# MergenElektronik_Developing-Board_ESP32.net
KiCad netlist of a schematic drawn in EAGLE
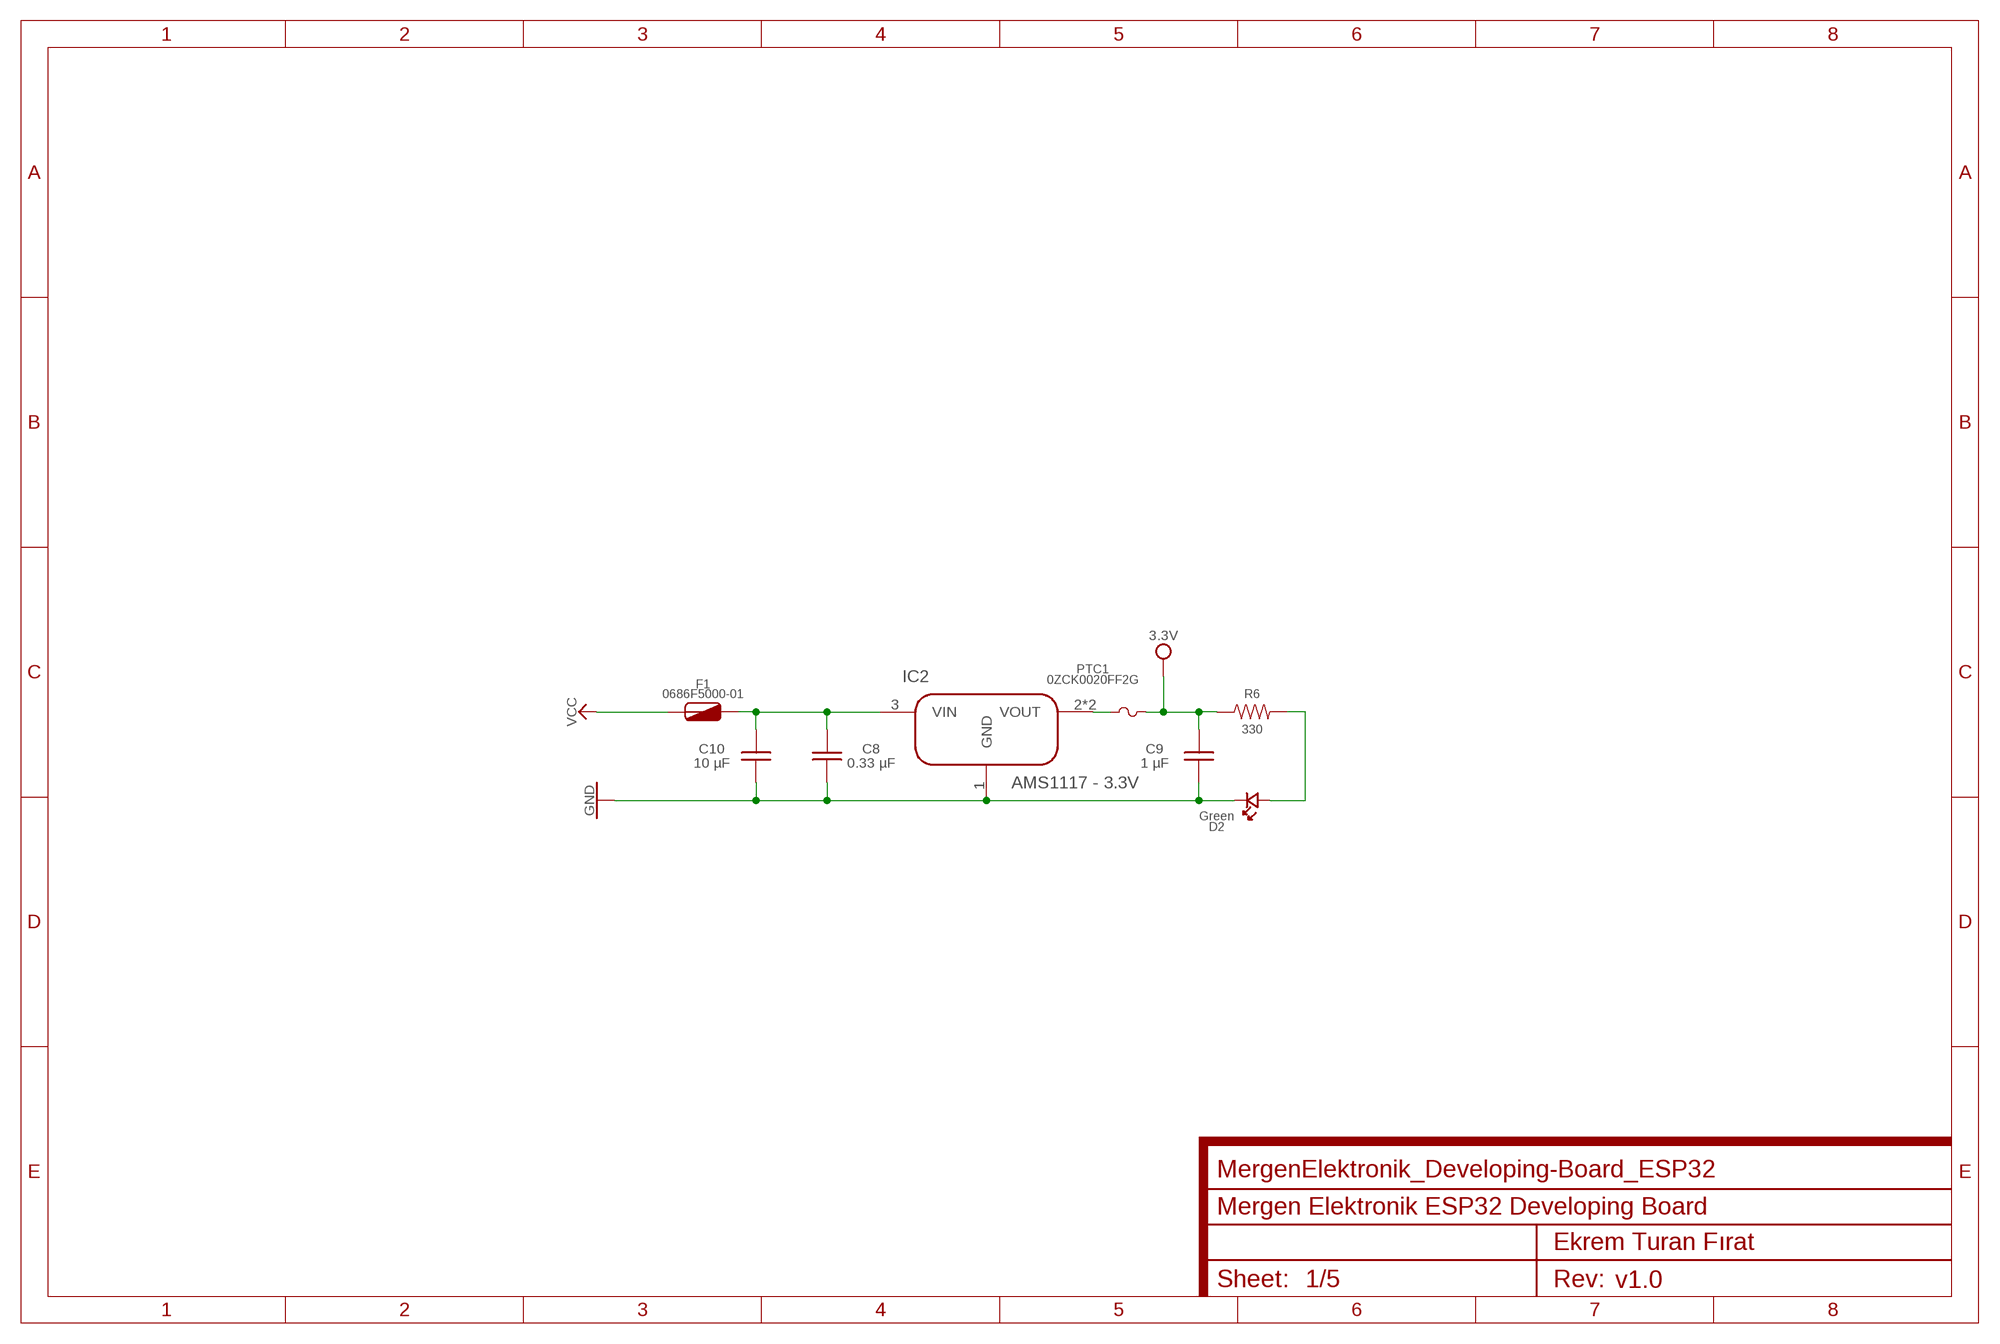
[diagram p0: schematic, sheet 1]
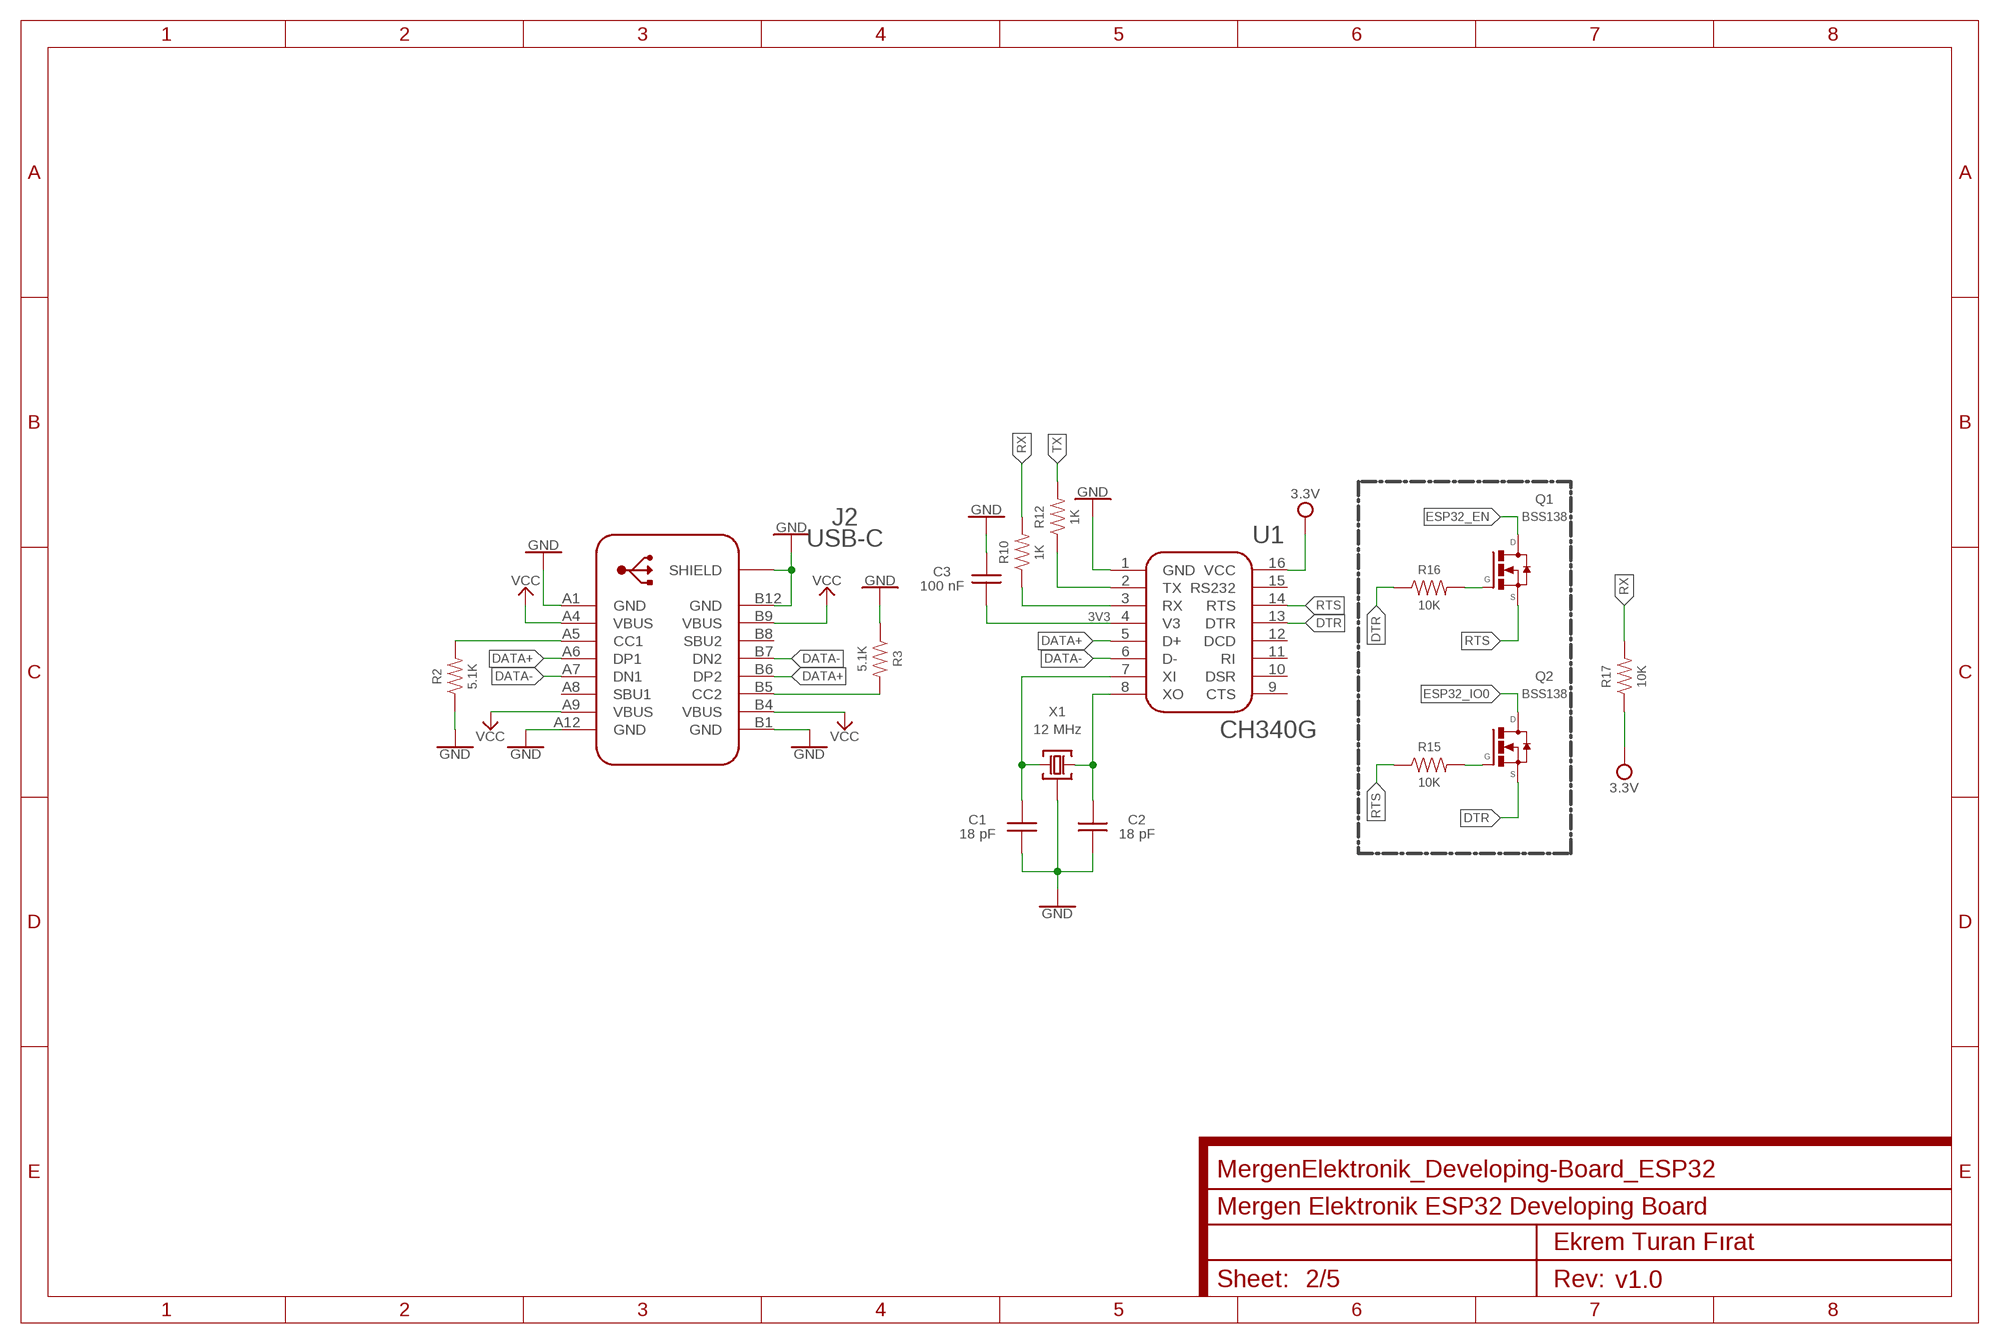
[diagram p1: schematic, sheet 2]
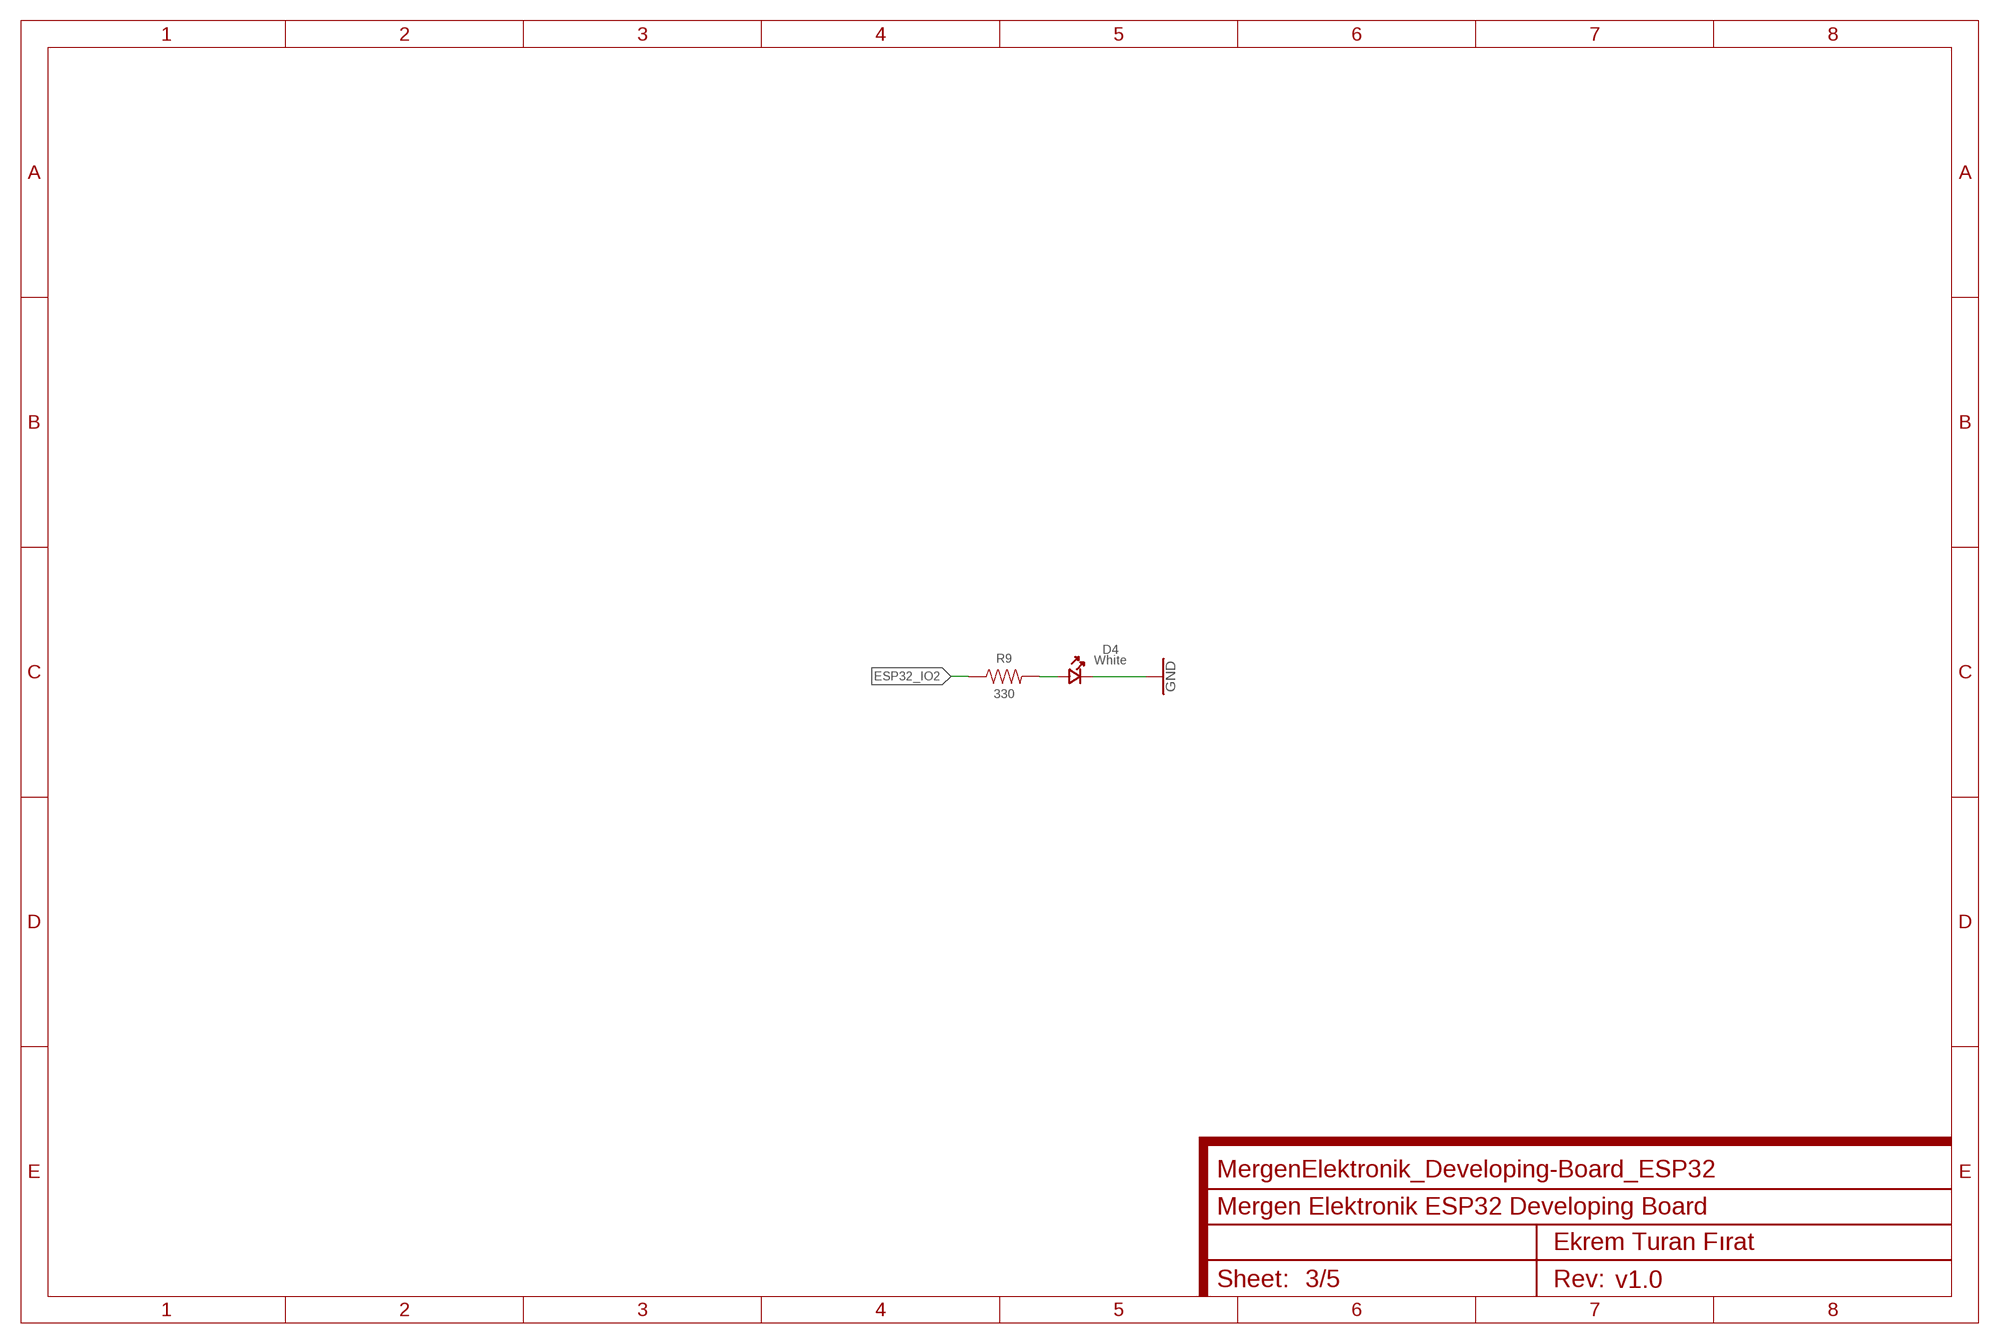
[diagram p2: schematic, sheet 3]
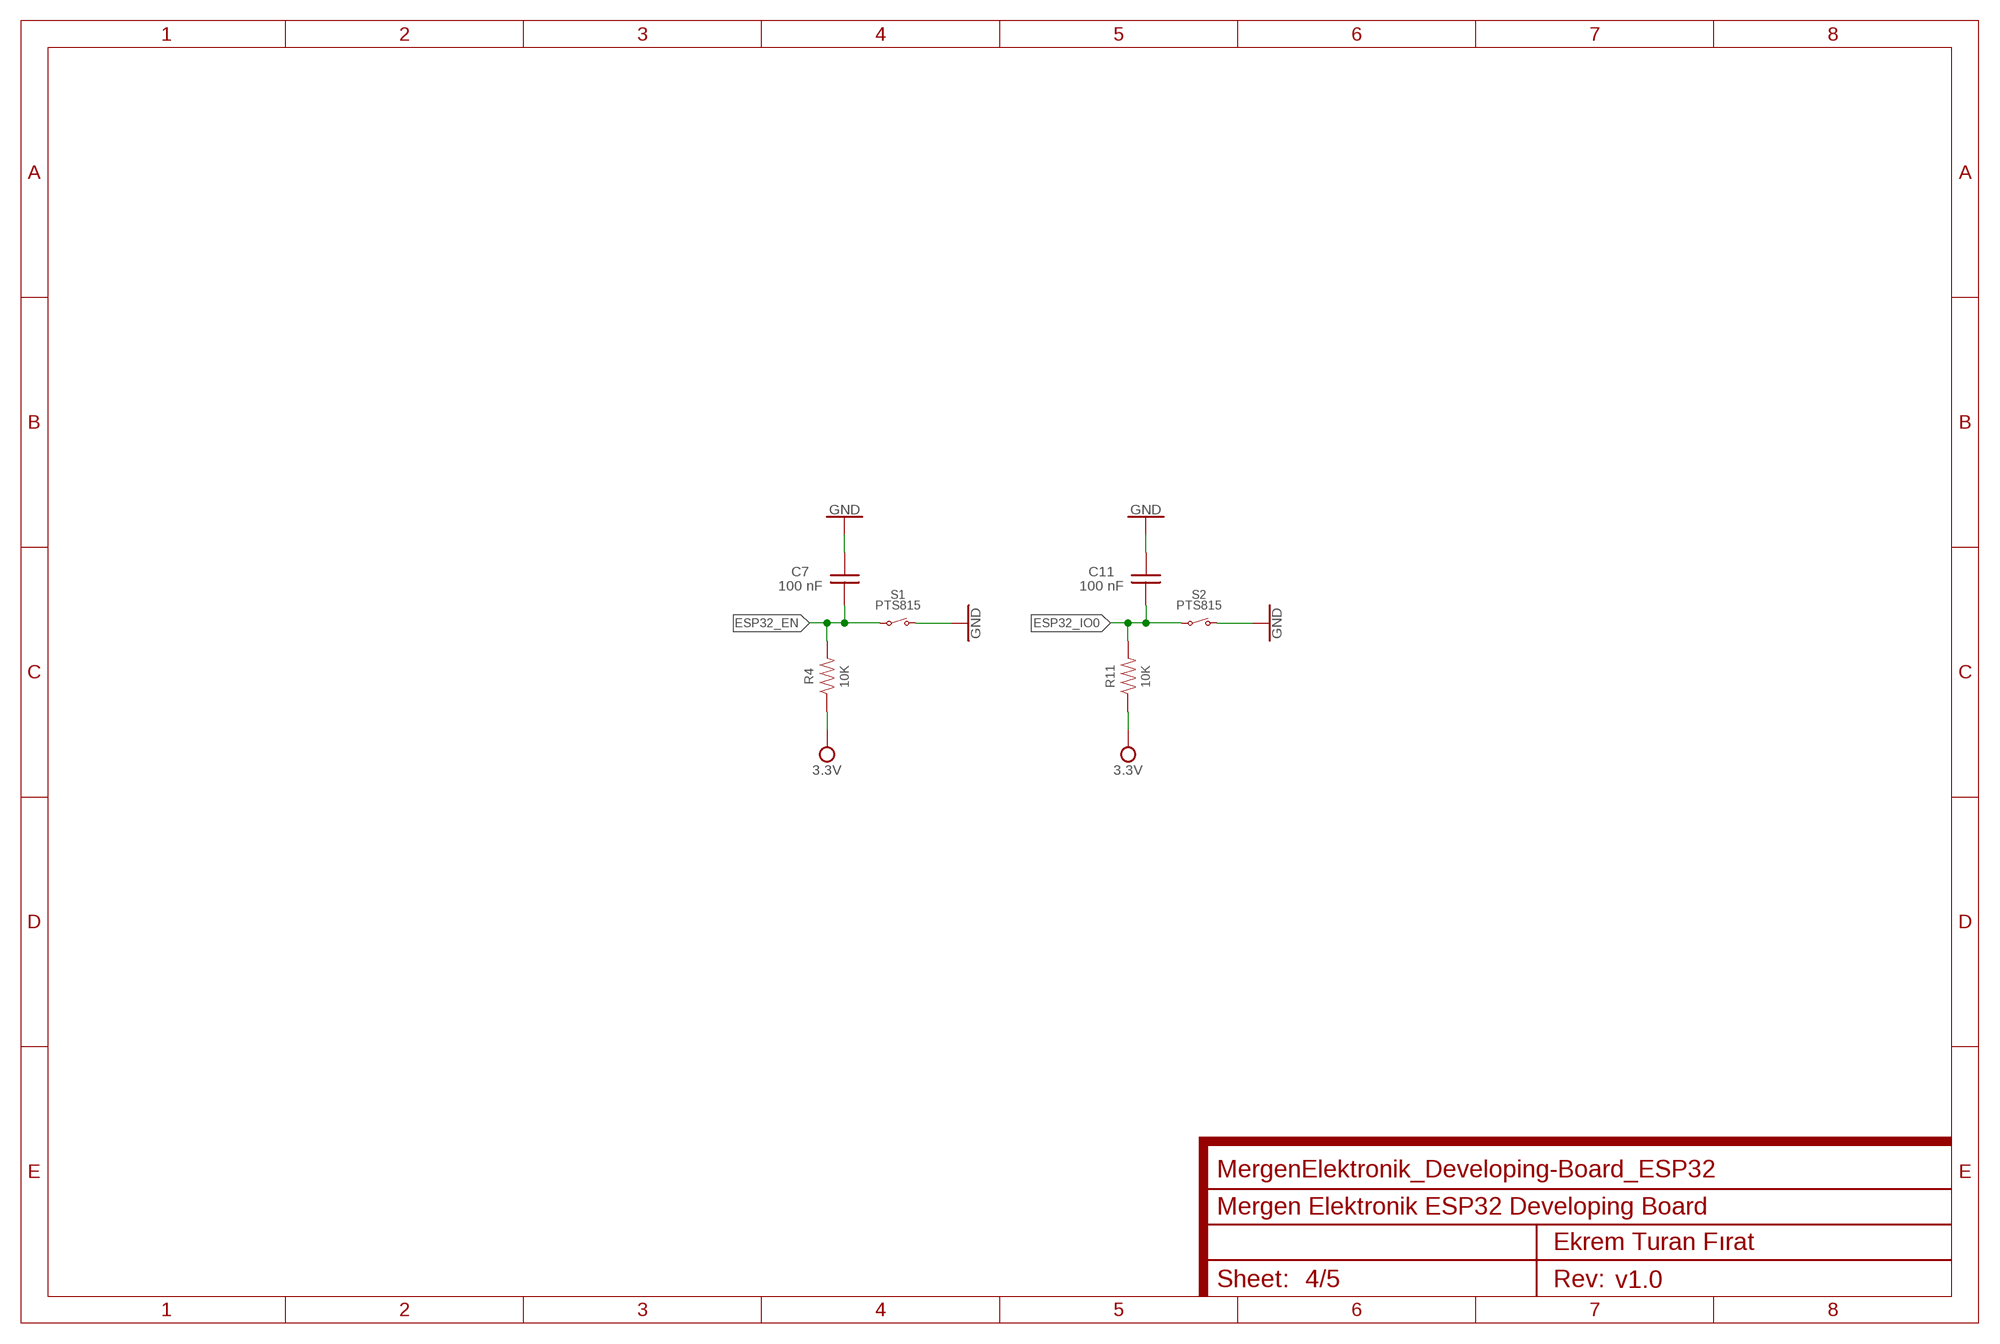
[diagram p3: schematic, sheet 4]
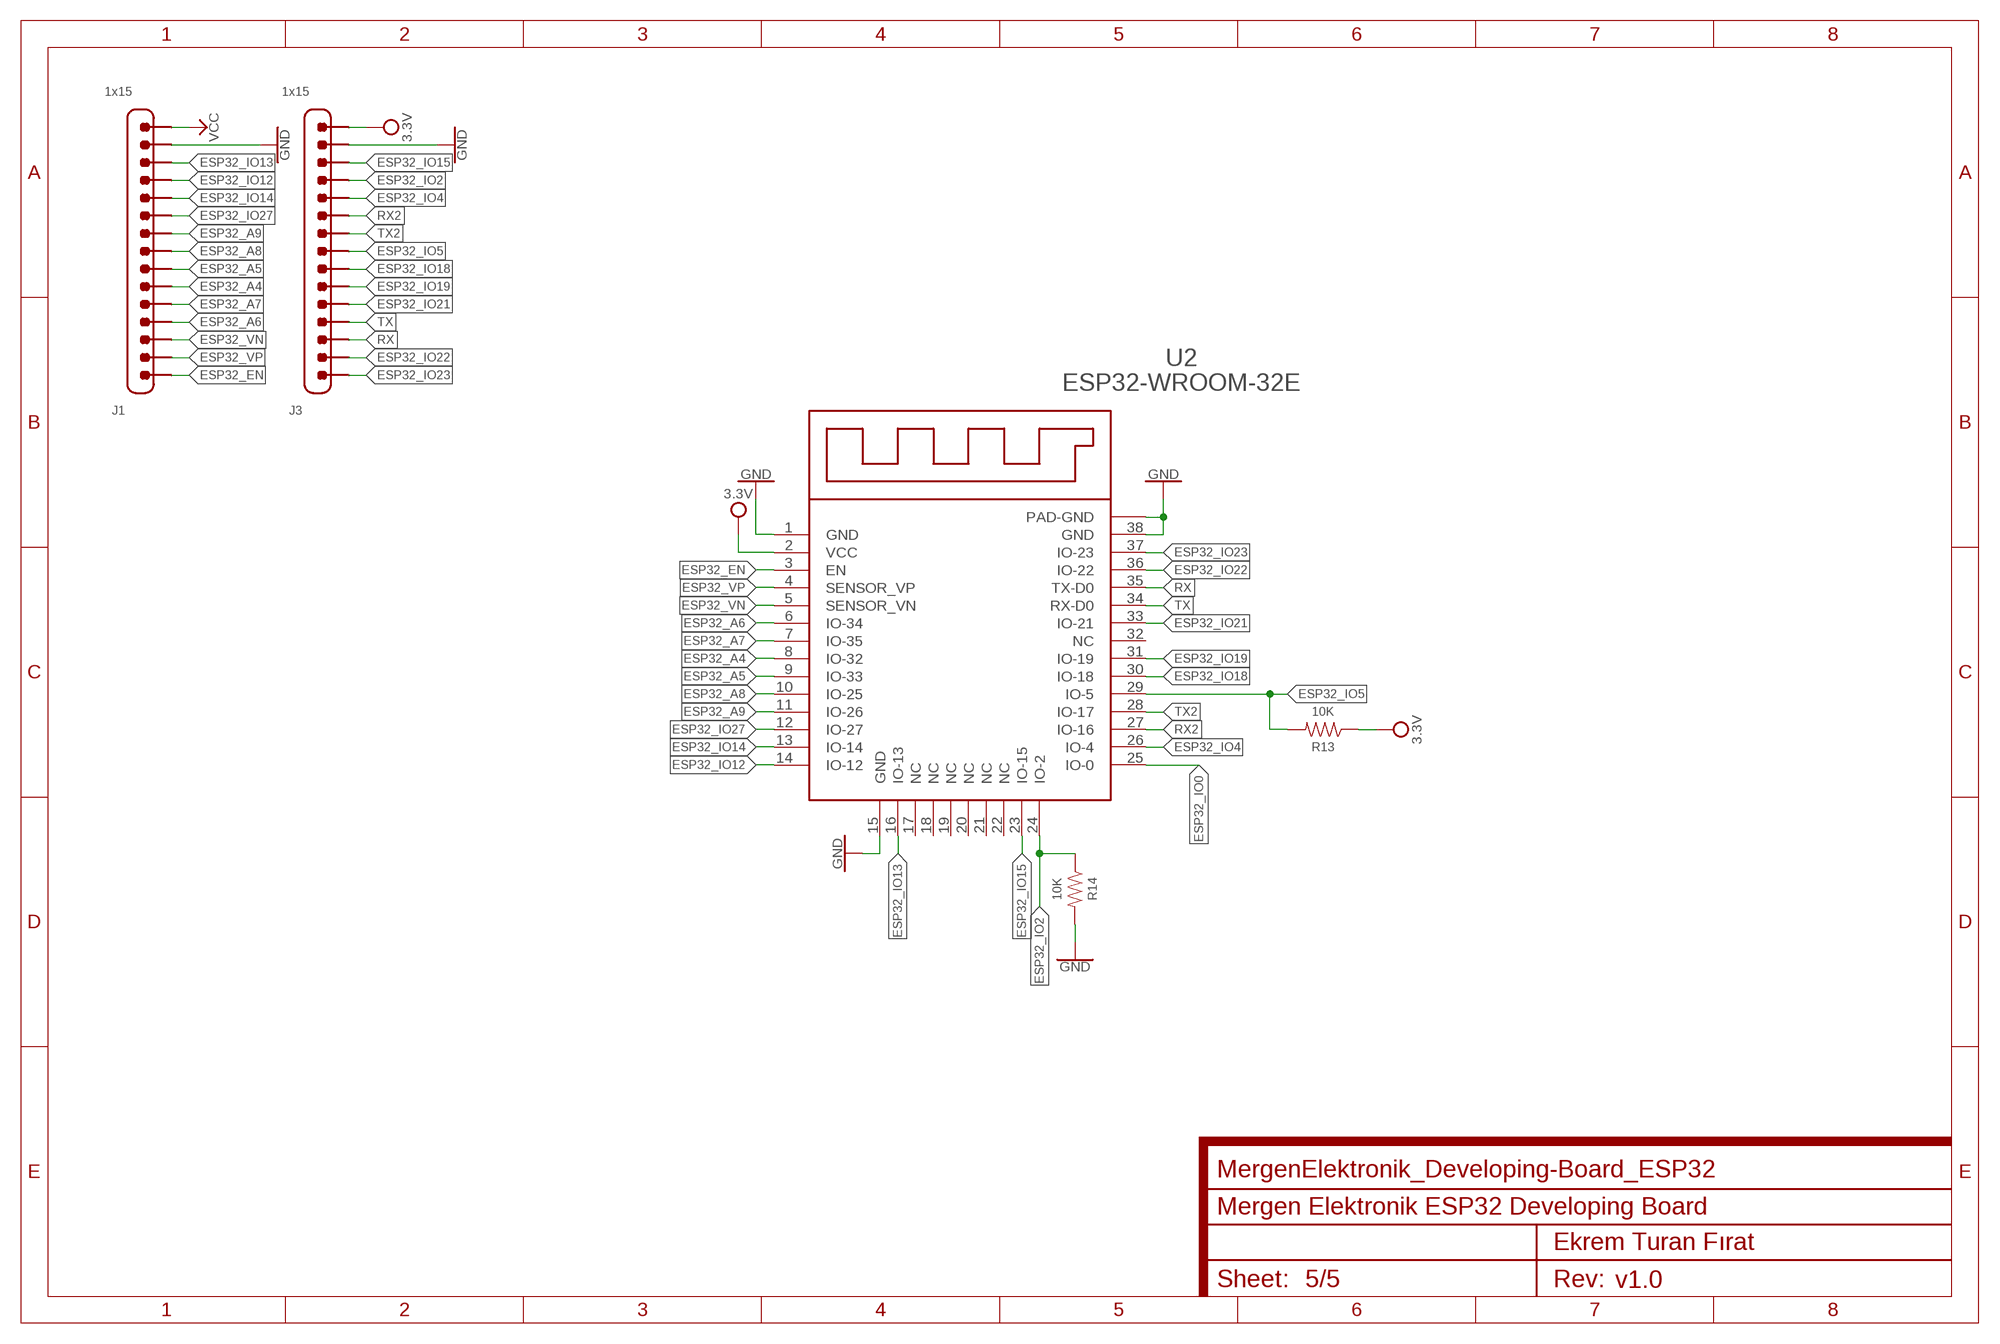
[diagram p4: schematic, sheet 5]

(export (version "E")
  (design (tool "Eeschema 10.0.6"))
  (components
    (comp (ref "C1")
      (value "18 pF")
      (footprint "eagle-import:0603")
      (fields (field (name "TOLERANCE") "5%") (field (name "VOLTAGE") "50V"))
      (libsource (lib "eagle-import") (part "NACHTELK_CAP-NONPOLAR-SMD_0603_18PF"))
    )
    (comp (ref "C2")
      (value "18 pF")
      (footprint "eagle-import:0603")
      (fields (field (name "TOLERANCE") "5%") (field (name "VOLTAGE") "50V"))
      (libsource (lib "eagle-import") (part "NACHTELK_CAP-NONPOLAR-SMD_0603_18PF"))
    )
    (comp (ref "C3")
      (value "100 nF")
      (footprint "eagle-import:0603")
      (fields (field (name "TOLERANCE") "10%") (field (name "VOLTAGE") "50V"))
      (libsource (lib "eagle-import") (part "NACHTELK_CAP-NONPOLAR-SMD_0603_100NF"))
    )
    (comp (ref "J2")
      (value "USB-C")
      (footprint "eagle-import:USB4105")
      (libsource (lib "eagle-import") (part "NACHTELK_USBCONNECTORS_C-USB4105"))
    )
    (comp (ref "Q1")
      (value "BSS138")
      (footprint "eagle-import:SOT-23")
      (libsource (lib "eagle-import") (part "NACHTELK_MOSFET_N-CH_SOT-23_STYLE-21_BSS138"))
    )
    (comp (ref "Q2")
      (value "BSS138")
      (footprint "eagle-import:SOT-23")
      (libsource (lib "eagle-import") (part "NACHTELK_MOSFET_N-CH_SOT-23_STYLE-21_BSS138"))
    )
    (comp (ref "R2")
      (value "5.1K")
      (footprint "eagle-import:0603")
      (fields (field (name "POWER") "1/10W") (field (name "TOLERANCE") "%1"))
      (libsource (lib "eagle-import") (part "NACHTELK_RES-SMD_0603_5.1K"))
    )
    (comp (ref "R3")
      (value "5.1K")
      (footprint "eagle-import:0603")
      (fields (field (name "POWER") "1/10W") (field (name "TOLERANCE") "%1"))
      (libsource (lib "eagle-import") (part "NACHTELK_RES-SMD_0603_5.1K"))
    )
    (comp (ref "R10")
      (value "1K")
      (footprint "eagle-import:0603")
      (fields (field (name "POWER") "1/10W") (field (name "TOLERANCE") "%5"))
      (libsource (lib "eagle-import") (part "NACHTELK_RES-SMD_0603_1K"))
    )
    (comp (ref "R12")
      (value "1K")
      (footprint "eagle-import:0603")
      (fields (field (name "POWER") "1/10W") (field (name "TOLERANCE") "%5"))
      (libsource (lib "eagle-import") (part "NACHTELK_RES-SMD_0603_1K"))
    )
    (comp (ref "R15")
      (value "10K")
      (footprint "eagle-import:0603")
      (fields (field (name "POWER") "1/10W") (field (name "TOLERANCE") "%5"))
      (libsource (lib "eagle-import") (part "NACHTELK_RES-SMD_0603_10K"))
    )
    (comp (ref "R16")
      (value "10K")
      (footprint "eagle-import:0603")
      (fields (field (name "POWER") "1/10W") (field (name "TOLERANCE") "%5"))
      (libsource (lib "eagle-import") (part "NACHTELK_RES-SMD_0603_10K"))
    )
    (comp (ref "R17")
      (value "10K")
      (footprint "eagle-import:0603")
      (fields (field (name "POWER") "1/10W") (field (name "TOLERANCE") "%5"))
      (libsource (lib "eagle-import") (part "NACHTELK_RES-SMD_0603_10K"))
    )
    (comp (ref "U1")
      (value "CH340G")
      (footprint "eagle-import:SOIC-16")
      (fields (field (name "VOLTAGE") "3.3V and 5V"))
      (libsource (lib "eagle-import") (part "NACHTELK_COMMUNICATION-UART_CH340"))
    )
    (comp (ref "X1")
      (value "12 MHz")
      (footprint "eagle-import:4-SMD")
      (fields (field (name "TOLERANCE") "±20ppm"))
      (libsource (lib "eagle-import") (part "NACHTELK_CRYSTALS_EXTERNAL-G"))
    )
    (comp (ref "D4")
      (value "White")
      (footprint "eagle-import:0603_WHİTE")
      (fields (field (name "VOLTAGE") "3.2V"))
      (libsource (lib "eagle-import") (part "NACHTELK_LED_SMD_0603_WHITE"))
    )
    (comp (ref "R9")
      (value "330")
      (footprint "eagle-import:0603")
      (fields (field (name "POWER") "1/10W") (field (name "TOLERANCE") "%5"))
      (libsource (lib "eagle-import") (part "NACHTELK_RES-SMD_0603_330R"))
    )
    (comp (ref "C8")
      (value "0.33 µF")
      (footprint "eagle-import:0603")
      (fields (field (name "TOLERANCE") "10%") (field (name "VOLTAGE") "50V"))
      (libsource (lib "eagle-import") (part "NACHTELK_CAP-NONPOLAR-SMD_0603_0.33UF"))
    )
    (comp (ref "C9")
      (value "1 µF")
      (footprint "eagle-import:0603")
      (fields (field (name "TOLERANCE") "10%") (field (name "VOLTAGE") "50V"))
      (libsource (lib "eagle-import") (part "NACHTELK_CAP-NONPOLAR-SMD_0603_1UF"))
    )
    (comp (ref "C10")
      (value "10 µF")
      (footprint "eagle-import:0603")
      (fields (field (name "TOLERANCE") "10%") (field (name "VOLTAGE") "25V"))
      (libsource (lib "eagle-import") (part "NACHTELK_CAP-NONPOLAR-SMD_0603_10UF"))
    )
    (comp (ref "D2")
      (value "Green")
      (footprint "eagle-import:0603_GREEN")
      (fields (field (name "VOLTAGE") "3.2V"))
      (libsource (lib "eagle-import") (part "NACHTELK_LED_SMD_0603_GREEN"))
    )
    (comp (ref "F1")
      (value "0686F5000-01")
      (footprint "eagle-import:0603")
      (libsource (lib "eagle-import") (part "NACHTELK_FUSES_SMD_0603_5A"))
    )
    (comp (ref "IC2")
      (value "AMS1117 - 3.3V")
      (footprint "eagle-import:SOT-223")
      (libsource (lib "eagle-import") (part "NACHTELK_LINEAR-REG_AMS1117_3.3V"))
    )
    (comp (ref "PTC1")
      (value "0ZCK0020FF2G")
      (footprint "eagle-import:0805")
      (fields (field (name "VOLTAGE") "9V"))
      (libsource (lib "eagle-import") (part "NACHHTELK_PTCS-SMD_0805_0ZCK0020FF2G"))
    )
    (comp (ref "R6")
      (value "330")
      (footprint "eagle-import:0603")
      (fields (field (name "POWER") "1/10W") (field (name "TOLERANCE") "%5"))
      (libsource (lib "eagle-import") (part "NACHTELK_RES-SMD_0603_330R"))
    )
    (comp (ref "C7")
      (value "100 nF")
      (footprint "eagle-import:0603")
      (fields (field (name "TOLERANCE") "10%") (field (name "VOLTAGE") "50V"))
      (libsource (lib "eagle-import") (part "NACHTELK_CAP-NONPOLAR-SMD_0603_100NF"))
    )
    (comp (ref "C11")
      (value "100 nF")
      (footprint "eagle-import:0603")
      (fields (field (name "TOLERANCE") "10%") (field (name "VOLTAGE") "50V"))
      (libsource (lib "eagle-import") (part "NACHTELK_CAP-NONPOLAR-SMD_0603_100NF"))
    )
    (comp (ref "R4")
      (value "10K")
      (footprint "eagle-import:0603")
      (fields (field (name "POWER") "1/10W") (field (name "TOLERANCE") "%5"))
      (libsource (lib "eagle-import") (part "NACHTELK_RES-SMD_0603_10K"))
    )
    (comp (ref "R11")
      (value "10K")
      (footprint "eagle-import:0603")
      (fields (field (name "POWER") "1/10W") (field (name "TOLERANCE") "%5"))
      (libsource (lib "eagle-import") (part "NACHTELK_RES-SMD_0603_10K"))
    )
    (comp (ref "S1")
      (value "PTS815")
      (footprint "eagle-import:PTS815")
      (fields (field (name "VOLTAGE") "12V"))
      (libsource (lib "eagle-import") (part "NACHTELK_BUTTONS_BUTTON_PTS815_PTS815"))
    )
    (comp (ref "S2")
      (value "PTS815")
      (footprint "eagle-import:PTS815")
      (fields (field (name "VOLTAGE") "12V"))
      (libsource (lib "eagle-import") (part "NACHTELK_BUTTONS_BUTTON_PTS815_PTS815"))
    )
    (comp (ref "J1")
      (value "1x15")
      (footprint "eagle-import:HEADER_1X15")
      (libsource (lib "eagle-import") (part "NACHTELK_HEADERCONNECTORS_15_MALE"))
    )
    (comp (ref "J3")
      (value "1x15")
      (footprint "eagle-import:HEADER_1X15")
      (libsource (lib "eagle-import") (part "NACHTELK_HEADERCONNECTORS_15_MALE"))
    )
    (comp (ref "R13")
      (value "10K")
      (footprint "eagle-import:0603")
      (fields (field (name "POWER") "1/10W") (field (name "TOLERANCE") "%5"))
      (libsource (lib "eagle-import") (part "NACHTELK_RES-SMD_0603_10K"))
    )
    (comp (ref "R14")
      (value "10K")
      (footprint "eagle-import:0603")
      (fields (field (name "POWER") "1/10W") (field (name "TOLERANCE") "%5"))
      (libsource (lib "eagle-import") (part "NACHTELK_RES-SMD_0603_10K"))
    )
    (comp (ref "U2")
      (value "ESP32-WROOM-32E")
      (footprint "eagle-import:38-SMD_MODULE")
      (fields (field (name "VOLTAGE") "3V up to 3,6"))
      (libsource (lib "eagle-import") (part "NACHTELK_MICROCONTROLLER_ESP_ESP32_WROOM_32E"))
    )
  )
  (nets
    (net (code "1") (name "3V3") (class "Default")
      (node (ref "C3") (pin "2") (pinfunction "2_2") (pintype "passive"))
      (node (ref "C9") (pin "1") (pinfunction "1_1") (pintype "passive"))
      (node (ref "J3") (pin "1") (pinfunction "P$1_1") (pintype "bidirectional"))
      (node (ref "PTC1") (pin "2") (pinfunction "2_2") (pintype "passive"))
      (node (ref "R11") (pin "1") (pinfunction "1_1") (pintype "passive"))
      (node (ref "R13") (pin "1") (pinfunction "1_1") (pintype "passive"))
      (node (ref "R17") (pin "1") (pinfunction "1_1") (pintype "passive"))
      (node (ref "R4") (pin "1") (pinfunction "1_1") (pintype "passive"))
      (node (ref "R6") (pin "1") (pinfunction "1_1") (pintype "passive"))
      (node (ref "U1") (pin "16") (pinfunction "VCC_16") (pintype "power_in"))
      (node (ref "U1") (pin "4") (pinfunction "V3_4") (pintype "bidirectional"))
      (node (ref "U2") (pin "2") (pinfunction "VCC_2") (pintype "power_in"))
    )
    (net (code "2") (name "DATA+") (class "Default")
      (node (ref "J2") (pin "A6") (pinfunction "DP1_A6") (pintype "bidirectional"))
      (node (ref "J2") (pin "B6") (pinfunction "DP2_B6") (pintype "bidirectional"))
      (node (ref "U1") (pin "5") (pinfunction "D+_5") (pintype "bidirectional"))
    )
    (net (code "3") (name "DATA-") (class "Default")
      (node (ref "J2") (pin "A7") (pinfunction "DN1_A7") (pintype "bidirectional"))
      (node (ref "J2") (pin "B7") (pinfunction "DN2_B7") (pintype "bidirectional"))
      (node (ref "U1") (pin "6") (pinfunction "D-_6") (pintype "bidirectional"))
    )
    (net (code "4") (name "DTR") (class "Default")
      (node (ref "Q2") (pin "2") (pinfunction "S_2") (pintype "passive"))
      (node (ref "R16") (pin "1") (pinfunction "1_1") (pintype "passive"))
      (node (ref "U1") (pin "13") (pinfunction "DTR_13") (pintype "bidirectional"))
    )
    (net (code "5") (name "ESP32_A4") (class "Default")
      (node (ref "J1") (pin "10") (pinfunction "P$10_10") (pintype "bidirectional"))
      (node (ref "U2") (pin "8") (pinfunction "IO-32_8") (pintype "bidirectional"))
    )
    (net (code "6") (name "ESP32_A5") (class "Default")
      (node (ref "J1") (pin "9") (pinfunction "P$9_9") (pintype "bidirectional"))
      (node (ref "U2") (pin "9") (pinfunction "IO-33_9") (pintype "bidirectional"))
    )
    (net (code "7") (name "ESP32_A6") (class "Default")
      (node (ref "J1") (pin "12") (pinfunction "P$12_12") (pintype "bidirectional"))
      (node (ref "U2") (pin "6") (pinfunction "IO-34_6") (pintype "bidirectional"))
    )
    (net (code "8") (name "ESP32_A7") (class "Default")
      (node (ref "J1") (pin "11") (pinfunction "P$11_11") (pintype "bidirectional"))
      (node (ref "U2") (pin "7") (pinfunction "IO-35_7") (pintype "bidirectional"))
    )
    (net (code "9") (name "ESP32_A8") (class "Default")
      (node (ref "J1") (pin "8") (pinfunction "P$8_8") (pintype "bidirectional"))
      (node (ref "U2") (pin "10") (pinfunction "IO-25_10") (pintype "bidirectional"))
    )
    (net (code "10") (name "ESP32_A9") (class "Default")
      (node (ref "J1") (pin "7") (pinfunction "P$7_7") (pintype "bidirectional"))
      (node (ref "U2") (pin "11") (pinfunction "IO-26_11") (pintype "bidirectional"))
    )
    (net (code "11") (name "ESP32_EN") (class "Default")
      (node (ref "C7") (pin "2") (pinfunction "2_2") (pintype "passive"))
      (node (ref "J1") (pin "15") (pinfunction "P$15_15") (pintype "bidirectional"))
      (node (ref "Q1") (pin "3") (pinfunction "D_3") (pintype "passive"))
      (node (ref "R4") (pin "2") (pinfunction "2_2") (pintype "passive"))
      (node (ref "S1") (pin "1") (pinfunction "PASS1_1") (pintype "bidirectional"))
      (node (ref "S1") (pin "2") (pinfunction "PASS1_2") (pintype "bidirectional"))
      (node (ref "U2") (pin "3") (pinfunction "EN_3") (pintype "input"))
    )
    (net (code "12") (name "ESP32_IO0") (class "Default")
      (node (ref "C11") (pin "2") (pinfunction "2_2") (pintype "passive"))
      (node (ref "Q2") (pin "3") (pinfunction "D_3") (pintype "passive"))
      (node (ref "R11") (pin "2") (pinfunction "2_2") (pintype "passive"))
      (node (ref "S2") (pin "1") (pinfunction "PASS1_1") (pintype "bidirectional"))
      (node (ref "S2") (pin "2") (pinfunction "PASS1_2") (pintype "bidirectional"))
      (node (ref "U2") (pin "25") (pinfunction "IO-0_25") (pintype "bidirectional"))
    )
    (net (code "13") (name "ESP32_IO2") (class "Default")
      (node (ref "J3") (pin "4") (pinfunction "P$4_4") (pintype "bidirectional"))
      (node (ref "R14") (pin "1") (pinfunction "1_1") (pintype "passive"))
      (node (ref "R9") (pin "1") (pinfunction "1_1") (pintype "passive"))
      (node (ref "U2") (pin "24") (pinfunction "IO-2_24") (pintype "bidirectional"))
    )
    (net (code "14") (name "ESP32_IO4") (class "Default")
      (node (ref "J3") (pin "5") (pinfunction "P$5_5") (pintype "bidirectional"))
      (node (ref "U2") (pin "26") (pinfunction "IO-4_26") (pintype "bidirectional"))
    )
    (net (code "15") (name "ESP32_IO5") (class "Default")
      (node (ref "J3") (pin "8") (pinfunction "P$8_8") (pintype "bidirectional"))
      (node (ref "R13") (pin "2") (pinfunction "2_2") (pintype "passive"))
      (node (ref "U2") (pin "29") (pinfunction "IO-5_29") (pintype "bidirectional"))
    )
    (net (code "16") (name "ESP32_IO12") (class "Default")
      (node (ref "J1") (pin "4") (pinfunction "P$4_4") (pintype "bidirectional"))
      (node (ref "U2") (pin "14") (pinfunction "IO-12_14") (pintype "bidirectional"))
    )
    (net (code "17") (name "ESP32_IO13") (class "Default")
      (node (ref "J1") (pin "3") (pinfunction "P$3_3") (pintype "bidirectional"))
      (node (ref "U2") (pin "16") (pinfunction "IO-13_16") (pintype "bidirectional"))
    )
    (net (code "18") (name "ESP32_IO14") (class "Default")
      (node (ref "J1") (pin "5") (pinfunction "P$5_5") (pintype "bidirectional"))
      (node (ref "U2") (pin "13") (pinfunction "IO-14_13") (pintype "bidirectional"))
    )
    (net (code "19") (name "ESP32_IO15") (class "Default")
      (node (ref "J3") (pin "3") (pinfunction "P$3_3") (pintype "bidirectional"))
      (node (ref "U2") (pin "23") (pinfunction "IO-15_23") (pintype "bidirectional"))
    )
    (net (code "20") (name "ESP32_IO18") (class "Default")
      (node (ref "J3") (pin "9") (pinfunction "P$9_9") (pintype "bidirectional"))
      (node (ref "U2") (pin "30") (pinfunction "IO-18_30") (pintype "bidirectional"))
    )
    (net (code "21") (name "ESP32_IO19") (class "Default")
      (node (ref "J3") (pin "10") (pinfunction "P$10_10") (pintype "bidirectional"))
      (node (ref "U2") (pin "31") (pinfunction "IO-19_31") (pintype "bidirectional"))
    )
    (net (code "22") (name "ESP32_IO21") (class "Default")
      (node (ref "J3") (pin "11") (pinfunction "P$11_11") (pintype "bidirectional"))
      (node (ref "U2") (pin "33") (pinfunction "IO-21_33") (pintype "bidirectional"))
    )
    (net (code "23") (name "ESP32_IO22") (class "Default")
      (node (ref "J3") (pin "14") (pinfunction "P$14_14") (pintype "bidirectional"))
      (node (ref "U2") (pin "36") (pinfunction "IO-22_36") (pintype "bidirectional"))
    )
    (net (code "24") (name "ESP32_IO23") (class "Default")
      (node (ref "J3") (pin "15") (pinfunction "P$15_15") (pintype "bidirectional"))
      (node (ref "U2") (pin "37") (pinfunction "IO-23_37") (pintype "bidirectional"))
    )
    (net (code "25") (name "ESP32_IO27") (class "Default")
      (node (ref "J1") (pin "6") (pinfunction "P$6_6") (pintype "bidirectional"))
      (node (ref "U2") (pin "12") (pinfunction "IO-27_12") (pintype "bidirectional"))
    )
    (net (code "26") (name "ESP32_VN") (class "Default")
      (node (ref "J1") (pin "13") (pinfunction "P$13_13") (pintype "bidirectional"))
      (node (ref "U2") (pin "5") (pinfunction "SENSOR_VN_5") (pintype "bidirectional"))
    )
    (net (code "27") (name "ESP32_VP") (class "Default")
      (node (ref "J1") (pin "14") (pinfunction "P$14_14") (pintype "bidirectional"))
      (node (ref "U2") (pin "4") (pinfunction "SENSOR_VP_4") (pintype "bidirectional"))
    )
    (net (code "28") (name "GND") (class "Default")
      (node (ref "C1") (pin "2") (pinfunction "2_2") (pintype "passive"))
      (node (ref "C10") (pin "2") (pinfunction "2_2") (pintype "passive"))
      (node (ref "C11") (pin "1") (pinfunction "1_1") (pintype "passive"))
      (node (ref "C2") (pin "2") (pinfunction "2_2") (pintype "passive"))
      (node (ref "C3") (pin "1") (pinfunction "1_1") (pintype "passive"))
      (node (ref "C7") (pin "1") (pinfunction "1_1") (pintype "passive"))
      (node (ref "C8") (pin "2") (pinfunction "2_2") (pintype "passive"))
      (node (ref "C9") (pin "2") (pinfunction "2_2") (pintype "passive"))
      (node (ref "D2") (pin "2") (pinfunction "KATOT_2") (pintype "passive"))
      (node (ref "D4") (pin "2") (pinfunction "KATOT_2") (pintype "passive"))
      (node (ref "IC2") (pin "1") (pinfunction "GND_1") (pintype "power_in"))
      (node (ref "J1") (pin "2") (pinfunction "P$2_2") (pintype "bidirectional"))
      (node (ref "J2") (pin "A1") (pinfunction "GND_A1") (pintype "power_in"))
      (node (ref "J2") (pin "A12") (pinfunction "GND_A12") (pintype "power_in"))
      (node (ref "J2") (pin "B1") (pinfunction "GND_B1") (pintype "power_in"))
      (node (ref "J2") (pin "B12") (pinfunction "GND_B12") (pintype "power_in"))
      (node (ref "J2") (pin "SH1") (pinfunction "SHIELD_SH1") (pintype "power_in"))
      (node (ref "J2") (pin "SH2") (pinfunction "SHIELD_SH2") (pintype "power_in"))
      (node (ref "J2") (pin "SH3") (pinfunction "SHIELD_SH3") (pintype "power_in"))
      (node (ref "J2") (pin "SH4") (pinfunction "SHIELD_SH4") (pintype "power_in"))
      (node (ref "J3") (pin "2") (pinfunction "P$2_2") (pintype "bidirectional"))
      (node (ref "R14") (pin "2") (pinfunction "2_2") (pintype "passive"))
      (node (ref "R2") (pin "1") (pinfunction "1_1") (pintype "passive"))
      (node (ref "R3") (pin "1") (pinfunction "1_1") (pintype "passive"))
      (node (ref "S1") (pin "3") (pinfunction "PASS2_3") (pintype "bidirectional"))
      (node (ref "S1") (pin "4") (pinfunction "PASS2_4") (pintype "bidirectional"))
      (node (ref "S2") (pin "3") (pinfunction "PASS2_3") (pintype "bidirectional"))
      (node (ref "S2") (pin "4") (pinfunction "PASS2_4") (pintype "bidirectional"))
      (node (ref "U1") (pin "1") (pinfunction "GND_1") (pintype "power_in"))
      (node (ref "U2") (pin "1") (pinfunction "GND_1") (pintype "power_in"))
      (node (ref "U2") (pin "15") (pinfunction "GND_15") (pintype "power_in"))
      (node (ref "U2") (pin "38") (pinfunction "GND_38") (pintype "power_in"))
      (node (ref "U2") (pin "48") (pinfunction "PAD-GND_48") (pintype "power_in"))
      (node (ref "U2") (pin "P$1") (pinfunction "PAD-GND_P$1") (pintype "power_in"))
      (node (ref "X1") (pin "GND@1") (pinfunction "P$3_GND@1") (pintype "power_in"))
      (node (ref "X1") (pin "GND@2") (pinfunction "P$3_GND@2") (pintype "power_in"))
    )
    (net (code "29") (name "Net-(D2-ANOT)") (class "Default")
      (node (ref "D2") (pin "1") (pinfunction "ANOT_1") (pintype "passive"))
      (node (ref "R6") (pin "2") (pinfunction "2_2") (pintype "passive"))
    )
    (net (code "30") (name "Net-(D4-ANOT)") (class "Default")
      (node (ref "D4") (pin "1") (pinfunction "ANOT_1") (pintype "passive"))
      (node (ref "R9") (pin "2") (pinfunction "2_2") (pintype "passive"))
    )
    (net (code "31") (name "Net-(IC2-VIN)") (class "Default")
      (node (ref "C10") (pin "1") (pinfunction "1_1") (pintype "passive"))
      (node (ref "C8") (pin "1") (pinfunction "1_1") (pintype "passive"))
      (node (ref "F1") (pin "2") (pinfunction "2_2") (pintype "passive"))
      (node (ref "IC2") (pin "3") (pinfunction "VIN_3") (pintype "input"))
    )
    (net (code "32") (name "Net-(IC2-VOUT-Pad2)") (class "Default")
      (node (ref "IC2") (pin "2") (pinfunction "VOUT_2") (pintype "output"))
      (node (ref "IC2") (pin "4") (pinfunction "VOUT_4") (pintype "output"))
      (node (ref "PTC1") (pin "1") (pinfunction "1_1") (pintype "passive"))
    )
    (net (code "33") (name "Net-(J2-CC1)") (class "Default")
      (node (ref "J2") (pin "A5") (pinfunction "CC1_A5") (pintype "bidirectional"))
      (node (ref "R2") (pin "2") (pinfunction "2_2") (pintype "passive"))
    )
    (net (code "34") (name "Net-(J2-CC2)") (class "Default")
      (node (ref "J2") (pin "B5") (pinfunction "CC2_B5") (pintype "bidirectional"))
      (node (ref "R3") (pin "2") (pinfunction "2_2") (pintype "passive"))
    )
    (net (code "35") (name "Net-(Q1-G)") (class "Default")
      (node (ref "Q1") (pin "1") (pinfunction "G_1") (pintype "passive"))
      (node (ref "R16") (pin "2") (pinfunction "2_2") (pintype "passive"))
    )
    (net (code "36") (name "Net-(Q2-G)") (class "Default")
      (node (ref "Q2") (pin "1") (pinfunction "G_1") (pintype "passive"))
      (node (ref "R15") (pin "2") (pinfunction "2_2") (pintype "passive"))
    )
    (net (code "37") (name "Net-(U1-RX)") (class "Default")
      (node (ref "R10") (pin "1") (pinfunction "1_1") (pintype "passive"))
      (node (ref "U1") (pin "3") (pinfunction "RX_3") (pintype "bidirectional"))
    )
    (net (code "38") (name "Net-(U1-TX)") (class "Default")
      (node (ref "R12") (pin "1") (pinfunction "1_1") (pintype "passive"))
      (node (ref "U1") (pin "2") (pinfunction "TX_2") (pintype "bidirectional"))
    )
    (net (code "39") (name "Net-(U1-XI)") (class "Default")
      (node (ref "C1") (pin "1") (pinfunction "1_1") (pintype "passive"))
      (node (ref "U1") (pin "7") (pinfunction "XI_7") (pintype "passive"))
      (node (ref "X1") (pin "3") (pinfunction "P$2_3") (pintype "passive"))
    )
    (net (code "40") (name "Net-(U1-XO)") (class "Default")
      (node (ref "C2") (pin "1") (pinfunction "1_1") (pintype "passive"))
      (node (ref "U1") (pin "8") (pinfunction "XO_8") (pintype "passive"))
      (node (ref "X1") (pin "1") (pinfunction "P$1_1") (pintype "passive"))
    )
    (net (code "41") (name "RTS") (class "Default")
      (node (ref "Q1") (pin "2") (pinfunction "S_2") (pintype "passive"))
      (node (ref "R15") (pin "1") (pinfunction "1_1") (pintype "passive"))
      (node (ref "U1") (pin "14") (pinfunction "RTS_14") (pintype "bidirectional"))
    )
    (net (code "42") (name "RX") (class "Default")
      (node (ref "J3") (pin "13") (pinfunction "P$13_13") (pintype "bidirectional"))
      (node (ref "R10") (pin "2") (pinfunction "2_2") (pintype "passive"))
      (node (ref "R17") (pin "2") (pinfunction "2_2") (pintype "passive"))
      (node (ref "U2") (pin "35") (pinfunction "TX-D0_35") (pintype "bidirectional"))
    )
    (net (code "43") (name "RX2") (class "Default")
      (node (ref "J3") (pin "6") (pinfunction "P$6_6") (pintype "bidirectional"))
      (node (ref "U2") (pin "27") (pinfunction "IO-16_27") (pintype "bidirectional"))
    )
    (net (code "44") (name "TX") (class "Default")
      (node (ref "J3") (pin "12") (pinfunction "P$12_12") (pintype "bidirectional"))
      (node (ref "R12") (pin "2") (pinfunction "2_2") (pintype "passive"))
      (node (ref "U2") (pin "34") (pinfunction "RX-D0_34") (pintype "bidirectional"))
    )
    (net (code "45") (name "TX2") (class "Default")
      (node (ref "J3") (pin "7") (pinfunction "P$7_7") (pintype "bidirectional"))
      (node (ref "U2") (pin "28") (pinfunction "IO-17_28") (pintype "bidirectional"))
    )
    (net (code "46") (name "VCC") (class "Default")
      (node (ref "F1") (pin "1") (pinfunction "1_1") (pintype "passive"))
      (node (ref "J1") (pin "1") (pinfunction "P$1_1") (pintype "bidirectional"))
      (node (ref "J2") (pin "A4") (pinfunction "VBUS_A4") (pintype "power_in"))
      (node (ref "J2") (pin "A9") (pinfunction "VBUS_A9") (pintype "power_in"))
      (node (ref "J2") (pin "B4") (pinfunction "VBUS_B4") (pintype "power_in"))
      (node (ref "J2") (pin "B9") (pinfunction "VBUS_B9") (pintype "power_in"))
    )
    (net (code "47") (name "unconnected-(J2-SBU1-PadA8)") (class "Default")
      (node (ref "J2") (pin "A8") (pinfunction "SBU1_A8") (pintype "bidirectional"))
    )
    (net (code "48") (name "unconnected-(J2-SBU2-PadB8)") (class "Default")
      (node (ref "J2") (pin "B8") (pinfunction "SBU2_B8") (pintype "bidirectional"))
    )
    (net (code "49") (name "unconnected-(U1-CTS-Pad9)") (class "Default")
      (node (ref "U1") (pin "9") (pinfunction "CTS_9") (pintype "bidirectional"))
    )
    (net (code "50") (name "unconnected-(U1-DCD-Pad12)") (class "Default")
      (node (ref "U1") (pin "12") (pinfunction "DCD_12") (pintype "bidirectional"))
    )
    (net (code "51") (name "unconnected-(U1-DSR-Pad10)") (class "Default")
      (node (ref "U1") (pin "10") (pinfunction "DSR_10") (pintype "bidirectional"))
    )
    (net (code "52") (name "unconnected-(U1-RI-Pad11)") (class "Default")
      (node (ref "U1") (pin "11") (pinfunction "RI_11") (pintype "bidirectional"))
    )
    (net (code "53") (name "unconnected-(U1-RS232-Pad15)") (class "Default")
      (node (ref "U1") (pin "15") (pinfunction "RS232_15") (pintype "bidirectional"))
    )
    (net (code "54") (name "unconnected-(U2-NC-Pad17)") (class "Default")
      (node (ref "U2") (pin "17") (pinfunction "NC_17") (pintype "no_connect"))
    )
    (net (code "55") (name "unconnected-(U2-NC-Pad18)") (class "Default")
      (node (ref "U2") (pin "18") (pinfunction "NC_18") (pintype "no_connect"))
    )
    (net (code "56") (name "unconnected-(U2-NC-Pad19)") (class "Default")
      (node (ref "U2") (pin "19") (pinfunction "NC_19") (pintype "no_connect"))
    )
    (net (code "57") (name "unconnected-(U2-NC-Pad20)") (class "Default")
      (node (ref "U2") (pin "20") (pinfunction "NC_20") (pintype "no_connect"))
    )
    (net (code "58") (name "unconnected-(U2-NC-Pad21)") (class "Default")
      (node (ref "U2") (pin "21") (pinfunction "NC_21") (pintype "no_connect"))
    )
    (net (code "59") (name "unconnected-(U2-NC-Pad22)") (class "Default")
      (node (ref "U2") (pin "22") (pinfunction "NC_22") (pintype "no_connect"))
    )
    (net (code "60") (name "unconnected-(U2-NC-Pad32)") (class "Default")
      (node (ref "U2") (pin "32") (pinfunction "NC_32") (pintype "no_connect"))
    )
  )
)
